# ENTRENADOR16F1939.net
KiCad netlist of a schematic drawn in EAGLE
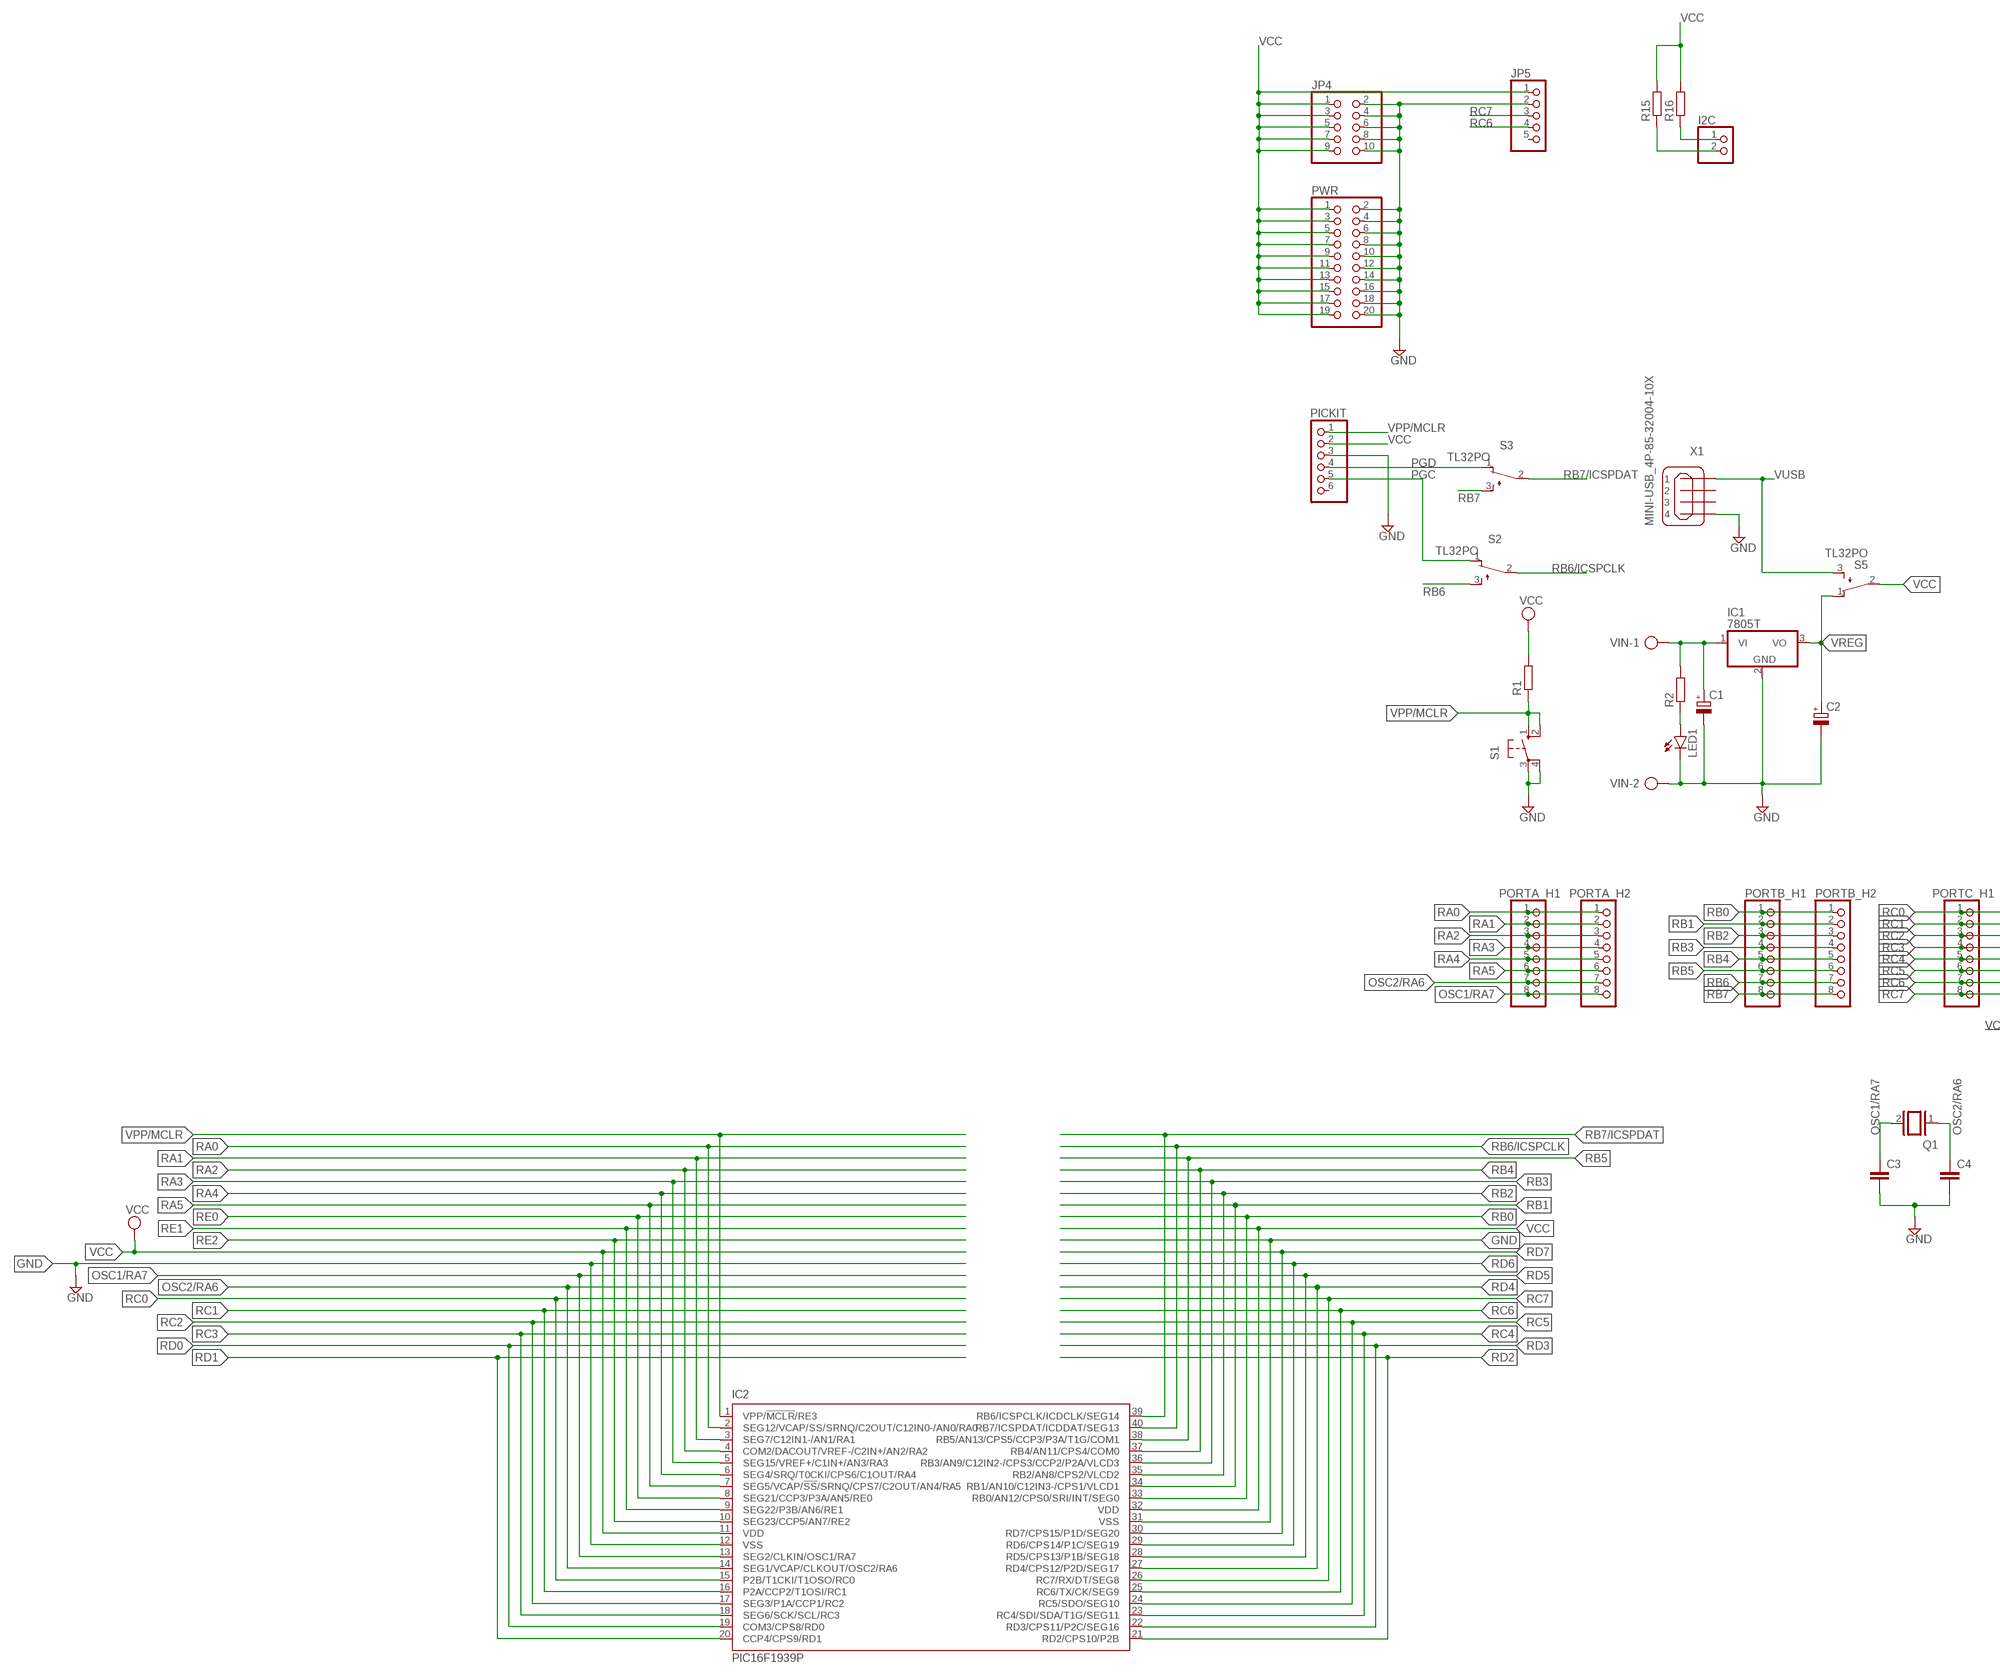
[diagram p0: schematic, sheet 1, part 1 of 2]
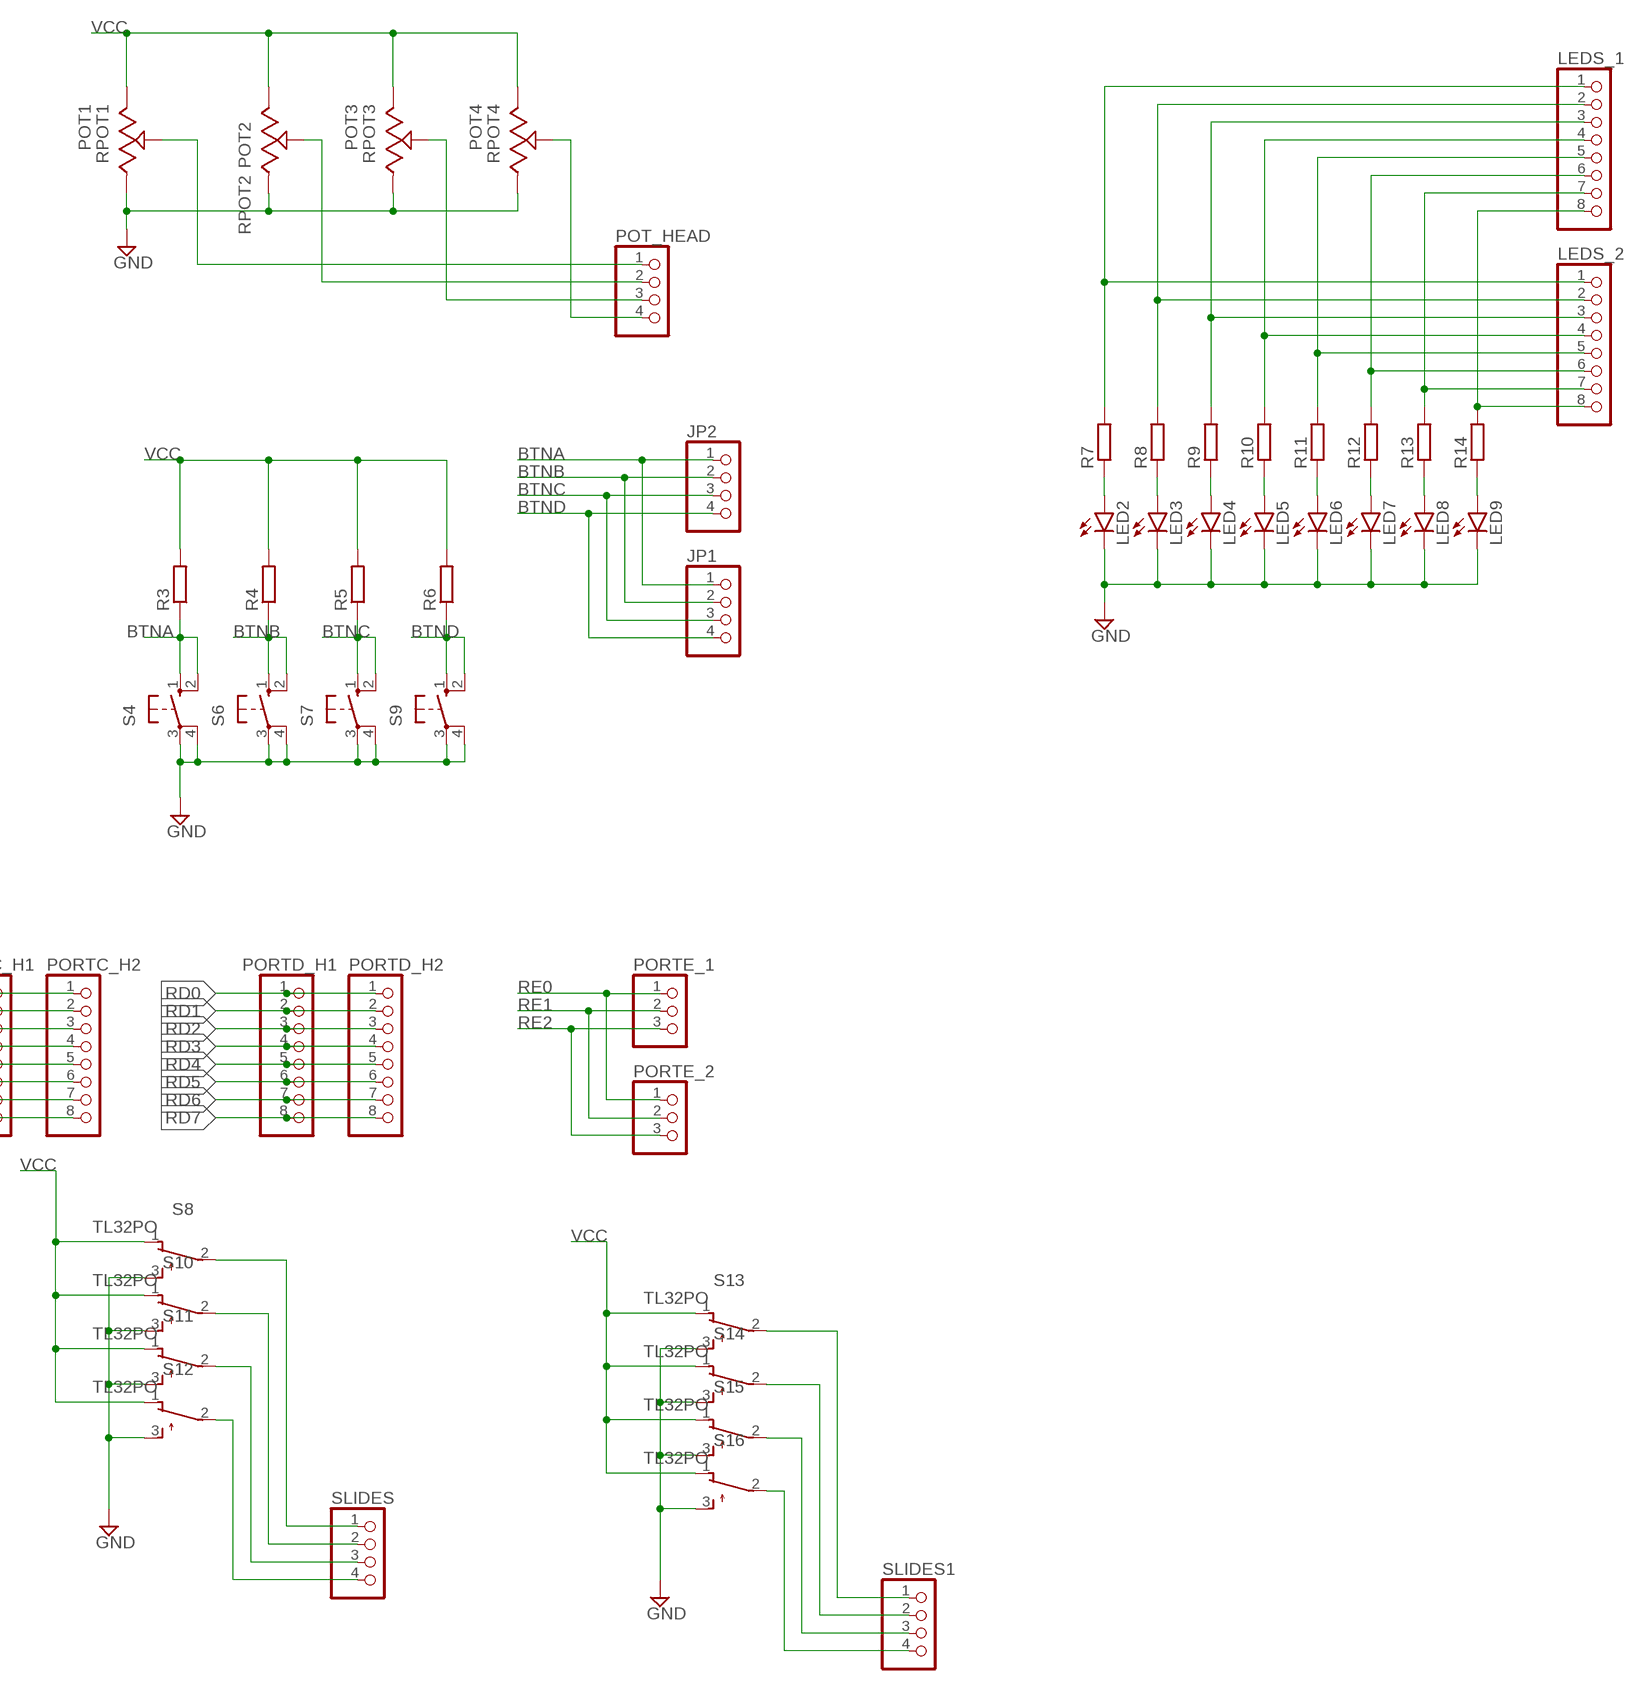
[diagram p1: schematic, sheet 1, part 2 of 2]

(export (version "E")
  (design (tool "Eeschema 10.0.6"))
  (components
    (comp (ref "C1")
      (value "CPOL-EUE2.5-6")
      (footprint "eagle-import:E2,5-6")
      (libsource (lib "eagle-import") (part "CPOL-EUE2.5-6"))
    )
    (comp (ref "C2")
      (value "CPOL-EUE2.5-6")
      (footprint "eagle-import:E2,5-6")
      (libsource (lib "eagle-import") (part "CPOL-EUE2.5-6"))
    )
    (comp (ref "C3")
      (value "C-EU025-024X044")
      (footprint "eagle-import:C025-024X044")
      (libsource (lib "eagle-import") (part "C-EU025-024X044"))
    )
    (comp (ref "C4")
      (value "C-EU025-024X044")
      (footprint "eagle-import:C025-024X044")
      (libsource (lib "eagle-import") (part "C-EU025-024X044"))
    )
    (comp (ref "I2C")
      (value "PINHD-1X2")
      (footprint "eagle-import:1X02")
      (libsource (lib "eagle-import") (part "PINHD-1X2"))
    )
    (comp (ref "IC1")
      (value "7805T")
      (footprint "eagle-import:TO220H")
      (libsource (lib "eagle-import") (part "78T05"))
    )
    (comp (ref "IC2")
      (value "PIC16F1939P")
      (footprint "eagle-import:DIL40")
      (fields (field (name "MPN") "PIC16F1939-I/P"))
      (libsource (lib "eagle-import") (part "PIC16F193?P9"))
    )
    (comp (ref "JP1")
      (value "PINHD-1X4")
      (footprint "eagle-import:1X04")
      (libsource (lib "eagle-import") (part "PINHD-1X4"))
    )
    (comp (ref "JP2")
      (value "PINHD-1X4")
      (footprint "eagle-import:1X04")
      (libsource (lib "eagle-import") (part "PINHD-1X4"))
    )
    (comp (ref "JP4")
      (value "PINHD-2X5")
      (footprint "eagle-import:2X05")
      (libsource (lib "eagle-import") (part "PINHD-2X5"))
    )
    (comp (ref "JP5")
      (value "PINHD-1X5")
      (footprint "eagle-import:1X05")
      (libsource (lib "eagle-import") (part "PINHD-1X5"))
    )
    (comp (ref "LED1")
      (value "LED3MM")
      (footprint "eagle-import:LED3MM")
      (libsource (lib "eagle-import") (part "LED3MM"))
    )
    (comp (ref "LED2")
      (value "LED3MM")
      (footprint "eagle-import:LED3MM")
      (libsource (lib "eagle-import") (part "LED3MM"))
    )
    (comp (ref "LED3")
      (value "LED3MM")
      (footprint "eagle-import:LED3MM")
      (libsource (lib "eagle-import") (part "LED3MM"))
    )
    (comp (ref "LED4")
      (value "LED3MM")
      (footprint "eagle-import:LED3MM")
      (libsource (lib "eagle-import") (part "LED3MM"))
    )
    (comp (ref "LED5")
      (value "LED3MM")
      (footprint "eagle-import:LED3MM")
      (libsource (lib "eagle-import") (part "LED3MM"))
    )
    (comp (ref "LED6")
      (value "LED3MM")
      (footprint "eagle-import:LED3MM")
      (libsource (lib "eagle-import") (part "LED3MM"))
    )
    (comp (ref "LED7")
      (value "LED3MM")
      (footprint "eagle-import:LED3MM")
      (libsource (lib "eagle-import") (part "LED3MM"))
    )
    (comp (ref "LED8")
      (value "LED3MM")
      (footprint "eagle-import:LED3MM")
      (libsource (lib "eagle-import") (part "LED3MM"))
    )
    (comp (ref "LED9")
      (value "LED3MM")
      (footprint "eagle-import:LED3MM")
      (libsource (lib "eagle-import") (part "LED3MM"))
    )
    (comp (ref "LEDS_1")
      (value "PINHD-1X8")
      (footprint "eagle-import:1X08")
      (libsource (lib "eagle-import") (part "PINHD-1X8"))
    )
    (comp (ref "LEDS_2")
      (value "PINHD-1X8")
      (footprint "eagle-import:1X08")
      (libsource (lib "eagle-import") (part "PINHD-1X8"))
    )
    (comp (ref "PICKIT")
      (value "PINHD-1X6")
      (footprint "eagle-import:1X06")
      (libsource (lib "eagle-import") (part "PINHD-1X6"))
    )
    (comp (ref "PORTA_H1")
      (value "PINHD-1X8")
      (footprint "eagle-import:1X08")
      (libsource (lib "eagle-import") (part "PINHD-1X8"))
    )
    (comp (ref "PORTA_H2")
      (value "PINHD-1X8")
      (footprint "eagle-import:1X08")
      (libsource (lib "eagle-import") (part "PINHD-1X8"))
    )
    (comp (ref "PORTB_H1")
      (value "PINHD-1X8")
      (footprint "eagle-import:1X08")
      (libsource (lib "eagle-import") (part "PINHD-1X8"))
    )
    (comp (ref "PORTB_H2")
      (value "PINHD-1X8")
      (footprint "eagle-import:1X08")
      (libsource (lib "eagle-import") (part "PINHD-1X8"))
    )
    (comp (ref "PORTC_H1")
      (value "PINHD-1X8")
      (footprint "eagle-import:1X08")
      (libsource (lib "eagle-import") (part "PINHD-1X8"))
    )
    (comp (ref "PORTC_H2")
      (value "PINHD-1X8")
      (footprint "eagle-import:1X08")
      (libsource (lib "eagle-import") (part "PINHD-1X8"))
    )
    (comp (ref "PORTD_H1")
      (value "PINHD-1X8")
      (footprint "eagle-import:1X08")
      (libsource (lib "eagle-import") (part "PINHD-1X8"))
    )
    (comp (ref "PORTD_H2")
      (value "PINHD-1X8")
      (footprint "eagle-import:1X08")
      (libsource (lib "eagle-import") (part "PINHD-1X8"))
    )
    (comp (ref "PORTE_1")
      (value "PINHD-1X3")
      (footprint "eagle-import:1X03")
      (libsource (lib "eagle-import") (part "PINHD-1X3"))
    )
    (comp (ref "PORTE_2")
      (value "PINHD-1X3")
      (footprint "eagle-import:1X03")
      (libsource (lib "eagle-import") (part "PINHD-1X3"))
    )
    (comp (ref "POT1")
      (value "RPOT1")
      (footprint "eagle-import:TRIM_3386P-1-101TLF")
      (fields (field (name "MF") "Bourns") (field (name "MP") "3386P-1-101TLF"))
      (libsource (lib "eagle-import") (part "3386P-1-101TLF"))
    )
    (comp (ref "POT2")
      (value "RPOT2")
      (footprint "eagle-import:TRIM_3386P-1-101TLF")
      (fields (field (name "MF") "Bourns") (field (name "MP") "3386P-1-101TLF"))
      (libsource (lib "eagle-import") (part "3386P-1-101TLF"))
    )
    (comp (ref "POT3")
      (value "RPOT3")
      (footprint "eagle-import:TRIM_3386P-1-101TLF")
      (fields (field (name "MF") "Bourns") (field (name "MP") "3386P-1-101TLF"))
      (libsource (lib "eagle-import") (part "3386P-1-101TLF"))
    )
    (comp (ref "POT4")
      (value "RPOT4")
      (footprint "eagle-import:TRIM_3386P-1-101TLF")
      (fields (field (name "MF") "Bourns") (field (name "MP") "3386P-1-101TLF"))
      (libsource (lib "eagle-import") (part "3386P-1-101TLF"))
    )
    (comp (ref "POT_HEAD")
      (value "PINHD-1X4")
      (footprint "eagle-import:1X04")
      (libsource (lib "eagle-import") (part "PINHD-1X4"))
    )
    (comp (ref "PWR")
      (value "PINHD-2X10")
      (footprint "eagle-import:2X10")
      (libsource (lib "eagle-import") (part "PINHD-2X10"))
    )
    (comp (ref "Q1")
      (value "XTAL/S")
      (footprint "eagle-import:QS")
      (libsource (lib "eagle-import") (part "XTAL/S"))
    )
    (comp (ref "R1")
      (value "R-EU_0204/7")
      (footprint "eagle-import:0204_7")
      (libsource (lib "eagle-import") (part "R-EU_0204/7"))
    )
    (comp (ref "R2")
      (value "R-EU_0204/7")
      (footprint "eagle-import:0204_7")
      (libsource (lib "eagle-import") (part "R-EU_0204/7"))
    )
    (comp (ref "R3")
      (value "R-EU_0204/7")
      (footprint "eagle-import:0204_7")
      (libsource (lib "eagle-import") (part "R-EU_0204/7"))
    )
    (comp (ref "R4")
      (value "R-EU_0204/7")
      (footprint "eagle-import:0204_7")
      (libsource (lib "eagle-import") (part "R-EU_0204/7"))
    )
    (comp (ref "R5")
      (value "R-EU_0204/7")
      (footprint "eagle-import:0204_7")
      (libsource (lib "eagle-import") (part "R-EU_0204/7"))
    )
    (comp (ref "R6")
      (value "R-EU_0204/7")
      (footprint "eagle-import:0204_7")
      (libsource (lib "eagle-import") (part "R-EU_0204/7"))
    )
    (comp (ref "R7")
      (value "R-EU_0204/7")
      (footprint "eagle-import:0204_7")
      (libsource (lib "eagle-import") (part "R-EU_0204/7"))
    )
    (comp (ref "R8")
      (value "R-EU_0204/7")
      (footprint "eagle-import:0204_7")
      (libsource (lib "eagle-import") (part "R-EU_0204/7"))
    )
    (comp (ref "R9")
      (value "R-EU_0204/7")
      (footprint "eagle-import:0204_7")
      (libsource (lib "eagle-import") (part "R-EU_0204/7"))
    )
    (comp (ref "R10")
      (value "R-EU_0204/7")
      (footprint "eagle-import:0204_7")
      (libsource (lib "eagle-import") (part "R-EU_0204/7"))
    )
    (comp (ref "R11")
      (value "R-EU_0204/7")
      (footprint "eagle-import:0204_7")
      (libsource (lib "eagle-import") (part "R-EU_0204/7"))
    )
    (comp (ref "R12")
      (value "R-EU_0204/7")
      (footprint "eagle-import:0204_7")
      (libsource (lib "eagle-import") (part "R-EU_0204/7"))
    )
    (comp (ref "R13")
      (value "R-EU_0204/7")
      (footprint "eagle-import:0204_7")
      (libsource (lib "eagle-import") (part "R-EU_0204/7"))
    )
    (comp (ref "R14")
      (value "R-EU_0204/7")
      (footprint "eagle-import:0204_7")
      (libsource (lib "eagle-import") (part "R-EU_0204/7"))
    )
    (comp (ref "R15")
      (value "R-EU_0204/7")
      (footprint "eagle-import:0204_7")
      (libsource (lib "eagle-import") (part "R-EU_0204/7"))
    )
    (comp (ref "R16")
      (value "R-EU_0204/7")
      (footprint "eagle-import:0204_7")
      (libsource (lib "eagle-import") (part "R-EU_0204/7"))
    )
    (comp (ref "S1")
      (value "10-XX")
      (footprint "eagle-import:B3F-10XX")
      (fields (field (name "MPN") "B3F-1000"))
      (libsource (lib "eagle-import") (part "10-XX"))
    )
    (comp (ref "S2")
      (value "TL32PO")
      (footprint "eagle-import:TL3XPO")
      (libsource (lib "eagle-import") (part "TL32PO"))
    )
    (comp (ref "S3")
      (value "TL32PO")
      (footprint "eagle-import:TL3XPO")
      (libsource (lib "eagle-import") (part "TL32PO"))
    )
    (comp (ref "S4")
      (value "10-XX")
      (footprint "eagle-import:B3F-10XX")
      (fields (field (name "MPN") "B3F-1000"))
      (libsource (lib "eagle-import") (part "10-XX"))
    )
    (comp (ref "S5")
      (value "TL32PO")
      (footprint "eagle-import:TL3XPO")
      (libsource (lib "eagle-import") (part "TL32PO"))
    )
    (comp (ref "S6")
      (value "10-XX")
      (footprint "eagle-import:B3F-10XX")
      (fields (field (name "MPN") "B3F-1000"))
      (libsource (lib "eagle-import") (part "10-XX"))
    )
    (comp (ref "S7")
      (value "10-XX")
      (footprint "eagle-import:B3F-10XX")
      (fields (field (name "MPN") "B3F-1000"))
      (libsource (lib "eagle-import") (part "10-XX"))
    )
    (comp (ref "S8")
      (value "TL32PO")
      (footprint "eagle-import:TL3XPO")
      (libsource (lib "eagle-import") (part "TL32PO"))
    )
    (comp (ref "S9")
      (value "10-XX")
      (footprint "eagle-import:B3F-10XX")
      (fields (field (name "MPN") "B3F-1000"))
      (libsource (lib "eagle-import") (part "10-XX"))
    )
    (comp (ref "S10")
      (value "TL32PO")
      (footprint "eagle-import:TL3XPO")
      (libsource (lib "eagle-import") (part "TL32PO"))
    )
    (comp (ref "S11")
      (value "TL32PO")
      (footprint "eagle-import:TL3XPO")
      (libsource (lib "eagle-import") (part "TL32PO"))
    )
    (comp (ref "S12")
      (value "TL32PO")
      (footprint "eagle-import:TL3XPO")
      (libsource (lib "eagle-import") (part "TL32PO"))
    )
    (comp (ref "S13")
      (value "TL32PO")
      (footprint "eagle-import:TL3XPO")
      (libsource (lib "eagle-import") (part "TL32PO"))
    )
    (comp (ref "S14")
      (value "TL32PO")
      (footprint "eagle-import:TL3XPO")
      (libsource (lib "eagle-import") (part "TL32PO"))
    )
    (comp (ref "S15")
      (value "TL32PO")
      (footprint "eagle-import:TL3XPO")
      (libsource (lib "eagle-import") (part "TL32PO"))
    )
    (comp (ref "S16")
      (value "TL32PO")
      (footprint "eagle-import:TL3XPO")
      (libsource (lib "eagle-import") (part "TL32PO"))
    )
    (comp (ref "SLIDES")
      (value "PINHD-1X4")
      (footprint "eagle-import:1X04")
      (libsource (lib "eagle-import") (part "PINHD-1X4"))
    )
    (comp (ref "SLIDES1")
      (value "PINHD-1X4")
      (footprint "eagle-import:1X04")
      (libsource (lib "eagle-import") (part "PINHD-1X4"))
    )
    (comp (ref "VIN")
      (value "AK300/2")
      (footprint "eagle-import:AK300_2")
      (libsource (lib "eagle-import") (part "AK300/2"))
    )
    (comp (ref "X1")
      (value "MINI-USB_4P-85-32004-10X")
      (footprint "eagle-import:85-32004-10X")
      (fields (field (name "SPICEPREFIX") "X"))
      (libsource (lib "eagle-import") (part "MINI-USB_4P-85-32004-10X"))
    )
  )
  (nets
    (net (code "1") (name "/BTNA") (class "Default")
      (node (ref "JP1") (pin "1") (pinfunction "1_1") (pintype "passive"))
      (node (ref "JP2") (pin "1") (pinfunction "1_1") (pintype "passive"))
      (node (ref "R3") (pin "1") (pinfunction "1_1") (pintype "passive"))
      (node (ref "S4") (pin "1") (pinfunction "S_1") (pintype "passive"))
      (node (ref "S4") (pin "2") (pinfunction "S1_2") (pintype "passive"))
    )
    (net (code "2") (name "/BTNB") (class "Default")
      (node (ref "JP1") (pin "2") (pinfunction "2_2") (pintype "passive"))
      (node (ref "JP2") (pin "2") (pinfunction "2_2") (pintype "passive"))
      (node (ref "R4") (pin "1") (pinfunction "1_1") (pintype "passive"))
      (node (ref "S6") (pin "1") (pinfunction "S_1") (pintype "passive"))
      (node (ref "S6") (pin "2") (pinfunction "S1_2") (pintype "passive"))
    )
    (net (code "3") (name "/BTNC") (class "Default")
      (node (ref "JP1") (pin "3") (pinfunction "3_3") (pintype "passive"))
      (node (ref "JP2") (pin "3") (pinfunction "3_3") (pintype "passive"))
      (node (ref "R5") (pin "1") (pinfunction "1_1") (pintype "passive"))
      (node (ref "S7") (pin "1") (pinfunction "S_1") (pintype "passive"))
      (node (ref "S7") (pin "2") (pinfunction "S1_2") (pintype "passive"))
    )
    (net (code "4") (name "/BTND") (class "Default")
      (node (ref "JP1") (pin "4") (pinfunction "4_4") (pintype "passive"))
      (node (ref "JP2") (pin "4") (pinfunction "4_4") (pintype "passive"))
      (node (ref "R6") (pin "1") (pinfunction "1_1") (pintype "passive"))
      (node (ref "S9") (pin "1") (pinfunction "S_1") (pintype "passive"))
      (node (ref "S9") (pin "2") (pinfunction "S1_2") (pintype "passive"))
    )
    (net (code "5") (name "/PGC") (class "Default")
      (node (ref "PICKIT") (pin "5") (pinfunction "5_5") (pintype "passive"))
      (node (ref "S2") (pin "1") (pinfunction "O_1") (pintype "passive"))
    )
    (net (code "6") (name "/PGD") (class "Default")
      (node (ref "PICKIT") (pin "4") (pinfunction "4_4") (pintype "passive"))
      (node (ref "S3") (pin "1") (pinfunction "O_1") (pintype "passive"))
    )
    (net (code "7") (name "/VUSB") (class "Default")
      (node (ref "S5") (pin "3") (pinfunction "S_3") (pintype "passive"))
      (node (ref "X1") (pin "1") (pinfunction "1_1") (pintype "passive"))
    )
    (net (code "8") (name "GND") (class "Default")
      (node (ref "C1") (pin "-") (pinfunction "-_-") (pintype "passive"))
      (node (ref "C2") (pin "-") (pinfunction "-_-") (pintype "passive"))
      (node (ref "C3") (pin "2") (pinfunction "2_2") (pintype "passive"))
      (node (ref "C4") (pin "2") (pinfunction "2_2") (pintype "passive"))
      (node (ref "IC1") (pin "2") (pinfunction "GND_2") (pintype "passive"))
      (node (ref "IC2") (pin "12") (pinfunction "VSS_12") (pintype "power_in"))
      (node (ref "IC2") (pin "31") (pinfunction "VSS_31") (pintype "power_in"))
      (node (ref "JP4") (pin "10") (pinfunction "10_10") (pintype "passive"))
      (node (ref "JP4") (pin "2") (pinfunction "2_2") (pintype "passive"))
      (node (ref "JP4") (pin "4") (pinfunction "4_4") (pintype "passive"))
      (node (ref "JP4") (pin "6") (pinfunction "6_6") (pintype "passive"))
      (node (ref "JP4") (pin "8") (pinfunction "8_8") (pintype "passive"))
      (node (ref "JP5") (pin "2") (pinfunction "2_2") (pintype "passive"))
      (node (ref "LED1") (pin "K") (pinfunction "C_K") (pintype "passive"))
      (node (ref "LED2") (pin "K") (pinfunction "C_K") (pintype "passive"))
      (node (ref "LED3") (pin "K") (pinfunction "C_K") (pintype "passive"))
      (node (ref "LED4") (pin "K") (pinfunction "C_K") (pintype "passive"))
      (node (ref "LED5") (pin "K") (pinfunction "C_K") (pintype "passive"))
      (node (ref "LED6") (pin "K") (pinfunction "C_K") (pintype "passive"))
      (node (ref "LED7") (pin "K") (pinfunction "C_K") (pintype "passive"))
      (node (ref "LED8") (pin "K") (pinfunction "C_K") (pintype "passive"))
      (node (ref "LED9") (pin "K") (pinfunction "C_K") (pintype "passive"))
      (node (ref "PICKIT") (pin "3") (pinfunction "3_3") (pintype "passive"))
      (node (ref "POT1") (pin "3") (pinfunction "CW_3") (pintype "passive"))
      (node (ref "POT2") (pin "3") (pinfunction "CW_3") (pintype "passive"))
      (node (ref "POT3") (pin "3") (pinfunction "CW_3") (pintype "passive"))
      (node (ref "POT4") (pin "3") (pinfunction "CW_3") (pintype "passive"))
      (node (ref "PWR") (pin "10") (pinfunction "10_10") (pintype "passive"))
      (node (ref "PWR") (pin "12") (pinfunction "12_12") (pintype "passive"))
      (node (ref "PWR") (pin "14") (pinfunction "14_14") (pintype "passive"))
      (node (ref "PWR") (pin "16") (pinfunction "16_16") (pintype "passive"))
      (node (ref "PWR") (pin "18") (pinfunction "18_18") (pintype "passive"))
      (node (ref "PWR") (pin "2") (pinfunction "2_2") (pintype "passive"))
      (node (ref "PWR") (pin "20") (pinfunction "20_20") (pintype "passive"))
      (node (ref "PWR") (pin "4") (pinfunction "4_4") (pintype "passive"))
      (node (ref "PWR") (pin "6") (pinfunction "6_6") (pintype "passive"))
      (node (ref "PWR") (pin "8") (pinfunction "8_8") (pintype "passive"))
      (node (ref "S1") (pin "3") (pinfunction "P_3") (pintype "passive"))
      (node (ref "S1") (pin "4") (pinfunction "P1_4") (pintype "passive"))
      (node (ref "S10") (pin "3") (pinfunction "S_3") (pintype "passive"))
      (node (ref "S11") (pin "3") (pinfunction "S_3") (pintype "passive"))
      (node (ref "S12") (pin "3") (pinfunction "S_3") (pintype "passive"))
      (node (ref "S13") (pin "3") (pinfunction "S_3") (pintype "passive"))
      (node (ref "S14") (pin "3") (pinfunction "S_3") (pintype "passive"))
      (node (ref "S15") (pin "3") (pinfunction "S_3") (pintype "passive"))
      (node (ref "S16") (pin "3") (pinfunction "S_3") (pintype "passive"))
      (node (ref "S4") (pin "3") (pinfunction "P_3") (pintype "passive"))
      (node (ref "S4") (pin "4") (pinfunction "P1_4") (pintype "passive"))
      (node (ref "S6") (pin "3") (pinfunction "P_3") (pintype "passive"))
      (node (ref "S6") (pin "4") (pinfunction "P1_4") (pintype "passive"))
      (node (ref "S7") (pin "3") (pinfunction "P_3") (pintype "passive"))
      (node (ref "S7") (pin "4") (pinfunction "P1_4") (pintype "passive"))
      (node (ref "S8") (pin "3") (pinfunction "S_3") (pintype "passive"))
      (node (ref "S9") (pin "3") (pinfunction "P_3") (pintype "passive"))
      (node (ref "S9") (pin "4") (pinfunction "P1_4") (pintype "passive"))
      (node (ref "VIN") (pin "2") (pinfunction "KL_2") (pintype "passive"))
      (node (ref "X1") (pin "4") (pinfunction "4_4") (pintype "passive"))
    )
    (net (code "9") (name "Net-(I2C-Pad1)") (class "Default")
      (node (ref "I2C") (pin "1") (pinfunction "1_1") (pintype "passive"))
      (node (ref "R16") (pin "1") (pinfunction "1_1") (pintype "passive"))
    )
    (net (code "10") (name "Net-(I2C-Pad2)") (class "Default")
      (node (ref "I2C") (pin "2") (pinfunction "2_2") (pintype "passive"))
      (node (ref "R15") (pin "1") (pinfunction "1_1") (pintype "passive"))
    )
    (net (code "11") (name "Net-(IC1-VI)") (class "Default")
      (node (ref "C1") (pin "+") (pinfunction "+_+") (pintype "passive"))
      (node (ref "IC1") (pin "1") (pinfunction "VI_1") (pintype "input"))
      (node (ref "R2") (pin "2") (pinfunction "2_2") (pintype "passive"))
      (node (ref "VIN") (pin "1") (pinfunction "KL_1") (pintype "passive"))
    )
    (net (code "12") (name "Net-(LED1-PadA)") (class "Default")
      (node (ref "LED1") (pin "A") (pinfunction "A_A") (pintype "passive"))
      (node (ref "R2") (pin "1") (pinfunction "1_1") (pintype "passive"))
    )
    (net (code "13") (name "Net-(LED2-PadA)") (class "Default")
      (node (ref "LED2") (pin "A") (pinfunction "A_A") (pintype "passive"))
      (node (ref "R7") (pin "1") (pinfunction "1_1") (pintype "passive"))
    )
    (net (code "14") (name "Net-(LED3-PadA)") (class "Default")
      (node (ref "LED3") (pin "A") (pinfunction "A_A") (pintype "passive"))
      (node (ref "R8") (pin "1") (pinfunction "1_1") (pintype "passive"))
    )
    (net (code "15") (name "Net-(LED4-PadA)") (class "Default")
      (node (ref "LED4") (pin "A") (pinfunction "A_A") (pintype "passive"))
      (node (ref "R9") (pin "1") (pinfunction "1_1") (pintype "passive"))
    )
    (net (code "16") (name "Net-(LED5-PadA)") (class "Default")
      (node (ref "LED5") (pin "A") (pinfunction "A_A") (pintype "passive"))
      (node (ref "R10") (pin "1") (pinfunction "1_1") (pintype "passive"))
    )
    (net (code "17") (name "Net-(LED6-PadA)") (class "Default")
      (node (ref "LED6") (pin "A") (pinfunction "A_A") (pintype "passive"))
      (node (ref "R11") (pin "1") (pinfunction "1_1") (pintype "passive"))
    )
    (net (code "18") (name "Net-(LED7-PadA)") (class "Default")
      (node (ref "LED7") (pin "A") (pinfunction "A_A") (pintype "passive"))
      (node (ref "R12") (pin "1") (pinfunction "1_1") (pintype "passive"))
    )
    (net (code "19") (name "Net-(LED8-PadA)") (class "Default")
      (node (ref "LED8") (pin "A") (pinfunction "A_A") (pintype "passive"))
      (node (ref "R13") (pin "1") (pinfunction "1_1") (pintype "passive"))
    )
    (net (code "20") (name "Net-(LED9-PadA)") (class "Default")
      (node (ref "LED9") (pin "A") (pinfunction "A_A") (pintype "passive"))
      (node (ref "R14") (pin "1") (pinfunction "1_1") (pintype "passive"))
    )
    (net (code "21") (name "Net-(LEDS_1-Pad1)") (class "Default")
      (node (ref "LEDS_1") (pin "1") (pinfunction "1_1") (pintype "passive"))
      (node (ref "LEDS_2") (pin "1") (pinfunction "1_1") (pintype "passive"))
      (node (ref "R7") (pin "2") (pinfunction "2_2") (pintype "passive"))
    )
    (net (code "22") (name "Net-(LEDS_1-Pad2)") (class "Default")
      (node (ref "LEDS_1") (pin "2") (pinfunction "2_2") (pintype "passive"))
      (node (ref "LEDS_2") (pin "2") (pinfunction "2_2") (pintype "passive"))
      (node (ref "R8") (pin "2") (pinfunction "2_2") (pintype "passive"))
    )
    (net (code "23") (name "Net-(LEDS_1-Pad3)") (class "Default")
      (node (ref "LEDS_1") (pin "3") (pinfunction "3_3") (pintype "passive"))
      (node (ref "LEDS_2") (pin "3") (pinfunction "3_3") (pintype "passive"))
      (node (ref "R9") (pin "2") (pinfunction "2_2") (pintype "passive"))
    )
    (net (code "24") (name "Net-(LEDS_1-Pad4)") (class "Default")
      (node (ref "LEDS_1") (pin "4") (pinfunction "4_4") (pintype "passive"))
      (node (ref "LEDS_2") (pin "4") (pinfunction "4_4") (pintype "passive"))
      (node (ref "R10") (pin "2") (pinfunction "2_2") (pintype "passive"))
    )
    (net (code "25") (name "Net-(LEDS_1-Pad5)") (class "Default")
      (node (ref "LEDS_1") (pin "5") (pinfunction "5_5") (pintype "passive"))
      (node (ref "LEDS_2") (pin "5") (pinfunction "5_5") (pintype "passive"))
      (node (ref "R11") (pin "2") (pinfunction "2_2") (pintype "passive"))
    )
    (net (code "26") (name "Net-(LEDS_1-Pad6)") (class "Default")
      (node (ref "LEDS_1") (pin "6") (pinfunction "6_6") (pintype "passive"))
      (node (ref "LEDS_2") (pin "6") (pinfunction "6_6") (pintype "passive"))
      (node (ref "R12") (pin "2") (pinfunction "2_2") (pintype "passive"))
    )
    (net (code "27") (name "Net-(LEDS_1-Pad7)") (class "Default")
      (node (ref "LEDS_1") (pin "7") (pinfunction "7_7") (pintype "passive"))
      (node (ref "LEDS_2") (pin "7") (pinfunction "7_7") (pintype "passive"))
      (node (ref "R13") (pin "2") (pinfunction "2_2") (pintype "passive"))
    )
    (net (code "28") (name "Net-(LEDS_1-Pad8)") (class "Default")
      (node (ref "LEDS_1") (pin "8") (pinfunction "8_8") (pintype "passive"))
      (node (ref "LEDS_2") (pin "8") (pinfunction "8_8") (pintype "passive"))
      (node (ref "R14") (pin "2") (pinfunction "2_2") (pintype "passive"))
    )
    (net (code "29") (name "Net-(POT1-WIPER)") (class "Default")
      (node (ref "POT1") (pin "2") (pinfunction "WIPER_2") (pintype "passive"))
      (node (ref "POT_HEAD") (pin "1") (pinfunction "1_1") (pintype "passive"))
    )
    (net (code "30") (name "Net-(POT2-WIPER)") (class "Default")
      (node (ref "POT2") (pin "2") (pinfunction "WIPER_2") (pintype "passive"))
      (node (ref "POT_HEAD") (pin "2") (pinfunction "2_2") (pintype "passive"))
    )
    (net (code "31") (name "Net-(POT3-WIPER)") (class "Default")
      (node (ref "POT3") (pin "2") (pinfunction "WIPER_2") (pintype "passive"))
      (node (ref "POT_HEAD") (pin "3") (pinfunction "3_3") (pintype "passive"))
    )
    (net (code "32") (name "Net-(POT4-WIPER)") (class "Default")
      (node (ref "POT4") (pin "2") (pinfunction "WIPER_2") (pintype "passive"))
      (node (ref "POT_HEAD") (pin "4") (pinfunction "4_4") (pintype "passive"))
    )
    (net (code "33") (name "Net-(S8-P)") (class "Default")
      (node (ref "S8") (pin "2") (pinfunction "P_2") (pintype "passive"))
      (node (ref "SLIDES") (pin "1") (pinfunction "1_1") (pintype "passive"))
    )
    (net (code "34") (name "Net-(S10-P)") (class "Default")
      (node (ref "S10") (pin "2") (pinfunction "P_2") (pintype "passive"))
      (node (ref "SLIDES") (pin "2") (pinfunction "2_2") (pintype "passive"))
    )
    (net (code "35") (name "Net-(S11-P)") (class "Default")
      (node (ref "S11") (pin "2") (pinfunction "P_2") (pintype "passive"))
      (node (ref "SLIDES") (pin "3") (pinfunction "3_3") (pintype "passive"))
    )
    (net (code "36") (name "Net-(S12-P)") (class "Default")
      (node (ref "S12") (pin "2") (pinfunction "P_2") (pintype "passive"))
      (node (ref "SLIDES") (pin "4") (pinfunction "4_4") (pintype "passive"))
    )
    (net (code "37") (name "Net-(S13-P)") (class "Default")
      (node (ref "S13") (pin "2") (pinfunction "P_2") (pintype "passive"))
      (node (ref "SLIDES1") (pin "1") (pinfunction "1_1") (pintype "passive"))
    )
    (net (code "38") (name "Net-(S14-P)") (class "Default")
      (node (ref "S14") (pin "2") (pinfunction "P_2") (pintype "passive"))
      (node (ref "SLIDES1") (pin "2") (pinfunction "2_2") (pintype "passive"))
    )
    (net (code "39") (name "Net-(S15-P)") (class "Default")
      (node (ref "S15") (pin "2") (pinfunction "P_2") (pintype "passive"))
      (node (ref "SLIDES1") (pin "3") (pinfunction "3_3") (pintype "passive"))
    )
    (net (code "40") (name "Net-(S16-P)") (class "Default")
      (node (ref "S16") (pin "2") (pinfunction "P_2") (pintype "passive"))
      (node (ref "SLIDES1") (pin "4") (pinfunction "4_4") (pintype "passive"))
    )
    (net (code "41") (name "OSC1{slash}RA7") (class "Default")
      (node (ref "C3") (pin "1") (pinfunction "1_1") (pintype "passive"))
      (node (ref "IC2") (pin "13") (pinfunction "SEG2/CLKIN/OSC1/RA7_13") (pintype "bidirectional"))
      (node (ref "PORTA_H1") (pin "8") (pinfunction "8_8") (pintype "passive"))
      (node (ref "PORTA_H2") (pin "8") (pinfunction "8_8") (pintype "passive"))
      (node (ref "Q1") (pin "2") (pinfunction "2_2") (pintype "passive"))
    )
    (net (code "42") (name "OSC2{slash}RA6") (class "Default")
      (node (ref "C4") (pin "1") (pinfunction "1_1") (pintype "passive"))
      (node (ref "IC2") (pin "14") (pinfunction "SEG1/VCAP/CLKOUT/OSC2/RA6_14") (pintype "bidirectional"))
      (node (ref "PORTA_H1") (pin "7") (pinfunction "7_7") (pintype "passive"))
      (node (ref "PORTA_H2") (pin "7") (pinfunction "7_7") (pintype "passive"))
      (node (ref "Q1") (pin "1") (pinfunction "1_1") (pintype "passive"))
    )
    (net (code "43") (name "RA0") (class "Default")
      (node (ref "IC2") (pin "2") (pinfunction "SEG12/VCAP/SS/SRNQ/C2OUT/C12IN0-/AN0/RA0_2") (pintype "bidirectional"))
      (node (ref "PORTA_H1") (pin "1") (pinfunction "1_1") (pintype "passive"))
      (node (ref "PORTA_H2") (pin "1") (pinfunction "1_1") (pintype "passive"))
    )
    (net (code "44") (name "RA1") (class "Default")
      (node (ref "IC2") (pin "3") (pinfunction "SEG7/C12IN1-/AN1/RA1_3") (pintype "bidirectional"))
      (node (ref "PORTA_H1") (pin "2") (pinfunction "2_2") (pintype "passive"))
      (node (ref "PORTA_H2") (pin "2") (pinfunction "2_2") (pintype "passive"))
    )
    (net (code "45") (name "RA2") (class "Default")
      (node (ref "IC2") (pin "4") (pinfunction "COM2/DACOUT/VREF-/C2IN+/AN2/RA2_4") (pintype "bidirectional"))
      (node (ref "PORTA_H1") (pin "3") (pinfunction "3_3") (pintype "passive"))
      (node (ref "PORTA_H2") (pin "3") (pinfunction "3_3") (pintype "passive"))
    )
    (net (code "46") (name "RA3") (class "Default")
      (node (ref "IC2") (pin "5") (pinfunction "SEG15/VREF+/C1IN+/AN3/RA3_5") (pintype "bidirectional"))
      (node (ref "PORTA_H1") (pin "4") (pinfunction "4_4") (pintype "passive"))
      (node (ref "PORTA_H2") (pin "4") (pinfunction "4_4") (pintype "passive"))
    )
    (net (code "47") (name "RA4") (class "Default")
      (node (ref "IC2") (pin "6") (pinfunction "SEG4/SRQ/T0CKI/CPS6/C1OUT/RA4_6") (pintype "bidirectional"))
      (node (ref "PORTA_H1") (pin "5") (pinfunction "5_5") (pintype "passive"))
      (node (ref "PORTA_H2") (pin "5") (pinfunction "5_5") (pintype "passive"))
    )
    (net (code "48") (name "RA5") (class "Default")
      (node (ref "IC2") (pin "7") (pinfunction "SEG5/VCAP/~{SS}/SRNQ/CPS7/C2OUT/AN4/RA5_7") (pintype "bidirectional"))
      (node (ref "PORTA_H1") (pin "6") (pinfunction "6_6") (pintype "passive"))
      (node (ref "PORTA_H2") (pin "6") (pinfunction "6_6") (pintype "passive"))
    )
    (net (code "49") (name "RB0") (class "Default")
      (node (ref "IC2") (pin "33") (pinfunction "RB0/AN12/CPS0/SRI/INT/SEG0_33") (pintype "bidirectional"))
      (node (ref "PORTB_H1") (pin "1") (pinfunction "1_1") (pintype "passive"))
      (node (ref "PORTB_H2") (pin "1") (pinfunction "1_1") (pintype "passive"))
    )
    (net (code "50") (name "RB1") (class "Default")
      (node (ref "IC2") (pin "34") (pinfunction "RB1/AN10/C12IN3-/CPS1/VLCD1_34") (pintype "bidirectional"))
      (node (ref "PORTB_H1") (pin "2") (pinfunction "2_2") (pintype "passive"))
      (node (ref "PORTB_H2") (pin "2") (pinfunction "2_2") (pintype "passive"))
    )
    (net (code "51") (name "RB2") (class "Default")
      (node (ref "IC2") (pin "35") (pinfunction "RB2/AN8/CPS2/VLCD2_35") (pintype "bidirectional"))
      (node (ref "PORTB_H1") (pin "3") (pinfunction "3_3") (pintype "passive"))
      (node (ref "PORTB_H2") (pin "3") (pinfunction "3_3") (pintype "passive"))
    )
    (net (code "52") (name "RB3") (class "Default")
      (node (ref "IC2") (pin "36") (pinfunction "RB3/AN9/C12IN2-/CPS3/CCP2/P2A/VLCD3_36") (pintype "bidirectional"))
      (node (ref "PORTB_H1") (pin "4") (pinfunction "4_4") (pintype "passive"))
      (node (ref "PORTB_H2") (pin "4") (pinfunction "4_4") (pintype "passive"))
    )
    (net (code "53") (name "RB4") (class "Default")
      (node (ref "IC2") (pin "37") (pinfunction "RB4/AN11/CPS4/COM0_37") (pintype "bidirectional"))
      (node (ref "PORTB_H1") (pin "5") (pinfunction "5_5") (pintype "passive"))
      (node (ref "PORTB_H2") (pin "5") (pinfunction "5_5") (pintype "passive"))
    )
    (net (code "54") (name "RB5") (class "Default")
      (node (ref "IC2") (pin "38") (pinfunction "RB5/AN13/CPS5/CCP3/P3A/T1G/COM1_38") (pintype "bidirectional"))
      (node (ref "PORTB_H1") (pin "6") (pinfunction "6_6") (pintype "passive"))
      (node (ref "PORTB_H2") (pin "6") (pinfunction "6_6") (pintype "passive"))
    )
    (net (code "55") (name "RB6") (class "Default")
      (node (ref "PORTB_H1") (pin "7") (pinfunction "7_7") (pintype "passive"))
      (node (ref "PORTB_H2") (pin "7") (pinfunction "7_7") (pintype "passive"))
      (node (ref "S2") (pin "3") (pinfunction "S_3") (pintype "passive"))
    )
    (net (code "56") (name "RB6{slash}ICSPCLK") (class "Default")
      (node (ref "IC2") (pin "40") (pinfunction "RB7/ICSPDAT/ICDDAT/SEG13_40") (pintype "bidirectional"))
      (node (ref "S2") (pin "2") (pinfunction "P_2") (pintype "passive"))
    )
    (net (code "57") (name "RB7") (class "Default")
      (node (ref "PORTB_H1") (pin "8") (pinfunction "8_8") (pintype "passive"))
      (node (ref "PORTB_H2") (pin "8") (pinfunction "8_8") (pintype "passive"))
      (node (ref "S3") (pin "3") (pinfunction "S_3") (pintype "passive"))
    )
    (net (code "58") (name "RB7{slash}ICSPDAT") (class "Default")
      (node (ref "IC2") (pin "39") (pinfunction "RB6/ICSPCLK/ICDCLK/SEG14_39") (pintype "bidirectional"))
      (node (ref "S3") (pin "2") (pinfunction "P_2") (pintype "passive"))
    )
    (net (code "59") (name "RC0") (class "Default")
      (node (ref "IC2") (pin "15") (pinfunction "P2B/T1CKI/T1OSO/RC0_15") (pintype "bidirectional"))
      (node (ref "PORTC_H1") (pin "1") (pinfunction "1_1") (pintype "passive"))
      (node (ref "PORTC_H2") (pin "1") (pinfunction "1_1") (pintype "passive"))
    )
    (net (code "60") (name "RC1") (class "Default")
      (node (ref "IC2") (pin "16") (pinfunction "P2A/CCP2/T1OSI/RC1_16") (pintype "bidirectional"))
      (node (ref "PORTC_H1") (pin "2") (pinfunction "2_2") (pintype "passive"))
      (node (ref "PORTC_H2") (pin "2") (pinfunction "2_2") (pintype "passive"))
    )
    (net (code "61") (name "RC2") (class "Default")
      (node (ref "IC2") (pin "17") (pinfunction "SEG3/P1A/CCP1/RC2_17") (pintype "bidirectional"))
      (node (ref "PORTC_H1") (pin "3") (pinfunction "3_3") (pintype "passive"))
      (node (ref "PORTC_H2") (pin "3") (pinfunction "3_3") (pintype "passive"))
    )
    (net (code "62") (name "RC3") (class "Default")
      (node (ref "IC2") (pin "18") (pinfunction "SEG6/SCK/SCL/RC3_18") (pintype "bidirectional"))
      (node (ref "PORTC_H1") (pin "4") (pinfunction "4_4") (pintype "passive"))
      (node (ref "PORTC_H2") (pin "4") (pinfunction "4_4") (pintype "passive"))
    )
    (net (code "63") (name "RC4") (class "Default")
      (node (ref "IC2") (pin "23") (pinfunction "RC4/SDI/SDA/T1G/SEG11_23") (pintype "bidirectional"))
      (node (ref "PORTC_H1") (pin "5") (pinfunction "5_5") (pintype "passive"))
      (node (ref "PORTC_H2") (pin "5") (pinfunction "5_5") (pintype "passive"))
    )
    (net (code "64") (name "RC5") (class "Default")
      (node (ref "IC2") (pin "24") (pinfunction "RC5/SDO/SEG10_24") (pintype "bidirectional"))
      (node (ref "PORTC_H1") (pin "6") (pinfunction "6_6") (pintype "passive"))
      (node (ref "PORTC_H2") (pin "6") (pinfunction "6_6") (pintype "passive"))
    )
    (net (code "65") (name "RC6") (class "Default")
      (node (ref "IC2") (pin "25") (pinfunction "RC6/TX/CK/SEG9_25") (pintype "bidirectional"))
      (node (ref "JP5") (pin "4") (pinfunction "4_4") (pintype "passive"))
      (node (ref "PORTC_H1") (pin "7") (pinfunction "7_7") (pintype "passive"))
      (node (ref "PORTC_H2") (pin "7") (pinfunction "7_7") (pintype "passive"))
    )
    (net (code "66") (name "RC7") (class "Default")
      (node (ref "IC2") (pin "26") (pinfunction "RC7/RX/DT/SEG8_26") (pintype "bidirectional"))
      (node (ref "JP5") (pin "3") (pinfunction "3_3") (pintype "passive"))
      (node (ref "PORTC_H1") (pin "8") (pinfunction "8_8") (pintype "passive"))
      (node (ref "PORTC_H2") (pin "8") (pinfunction "8_8") (pintype "passive"))
    )
    (net (code "67") (name "RD0") (class "Default")
      (node (ref "IC2") (pin "19") (pinfunction "COM3/CPS8/RD0_19") (pintype "bidirectional"))
      (node (ref "PORTD_H1") (pin "1") (pinfunction "1_1") (pintype "passive"))
      (node (ref "PORTD_H2") (pin "1") (pinfunction "1_1") (pintype "passive"))
    )
    (net (code "68") (name "RD1") (class "Default")
      (node (ref "IC2") (pin "20") (pinfunction "CCP4/CPS9/RD1_20") (pintype "bidirectional"))
      (node (ref "PORTD_H1") (pin "2") (pinfunction "2_2") (pintype "passive"))
      (node (ref "PORTD_H2") (pin "2") (pinfunction "2_2") (pintype "passive"))
    )
    (net (code "69") (name "RD2") (class "Default")
      (node (ref "IC2") (pin "21") (pinfunction "RD2/CPS10/P2B_21") (pintype "bidirectional"))
      (node (ref "PORTD_H1") (pin "3") (pinfunction "3_3") (pintype "passive"))
      (node (ref "PORTD_H2") (pin "3") (pinfunction "3_3") (pintype "passive"))
    )
    (net (code "70") (name "RD3") (class "Default")
      (node (ref "IC2") (pin "22") (pinfunction "RD3/CPS11/P2C/SEG16_22") (pintype "bidirectional"))
      (node (ref "PORTD_H1") (pin "4") (pinfunction "4_4") (pintype "passive"))
      (node (ref "PORTD_H2") (pin "4") (pinfunction "4_4") (pintype "passive"))
    )
    (net (code "71") (name "RD4") (class "Default")
      (node (ref "IC2") (pin "27") (pinfunction "RD4/CPS12/P2D/SEG17_27") (pintype "bidirectional"))
      (node (ref "PORTD_H1") (pin "5") (pinfunction "5_5") (pintype "passive"))
      (node (ref "PORTD_H2") (pin "5") (pinfunction "5_5") (pintype "passive"))
    )
    (net (code "72") (name "RD5") (class "Default")
      (node (ref "IC2") (pin "28") (pinfunction "RD5/CPS13/P1B/SEG18_28") (pintype "bidirectional"))
      (node (ref "PORTD_H1") (pin "6") (pinfunction "6_6") (pintype "passive"))
      (node (ref "PORTD_H2") (pin "6") (pinfunction "6_6") (pintype "passive"))
    )
    (net (code "73") (name "RD6") (class "Default")
      (node (ref "IC2") (pin "29") (pinfunction "RD6/CPS14/P1C/SEG19_29") (pintype "bidirectional"))
      (node (ref "PORTD_H1") (pin "7") (pinfunction "7_7") (pintype "passive"))
      (node (ref "PORTD_H2") (pin "7") (pinfunction "7_7") (pintype "passive"))
    )
    (net (code "74") (name "RD7") (class "Default")
      (node (ref "IC2") (pin "30") (pinfunction "RD7/CPS15/P1D/SEG20_30") (pintype "bidirectional"))
      (node (ref "PORTD_H1") (pin "8") (pinfunction "8_8") (pintype "passive"))
      (node (ref "PORTD_H2") (pin "8") (pinfunction "8_8") (pintype "passive"))
    )
    (net (code "75") (name "RE0") (class "Default")
      (node (ref "IC2") (pin "8") (pinfunction "SEG21/CCP3/P3A/AN5/RE0_8") (pintype "bidirectional"))
      (node (ref "PORTE_1") (pin "1") (pinfunction "1_1") (pintype "passive"))
      (node (ref "PORTE_2") (pin "1") (pinfunction "1_1") (pintype "passive"))
    )
    (net (code "76") (name "RE1") (class "Default")
      (node (ref "IC2") (pin "9") (pinfunction "SEG22/P3B/AN6/RE1_9") (pintype "bidirectional"))
      (node (ref "PORTE_1") (pin "2") (pinfunction "2_2") (pintype "passive"))
      (node (ref "PORTE_2") (pin "2") (pinfunction "2_2") (pintype "passive"))
    )
    (net (code "77") (name "RE2") (class "Default")
      (node (ref "IC2") (pin "10") (pinfunction "SEG23/CCP5/AN7/RE2_10") (pintype "bidirectional"))
      (node (ref "PORTE_1") (pin "3") (pinfunction "3_3") (pintype "passive"))
      (node (ref "PORTE_2") (pin "3") (pinfunction "3_3") (pintype "passive"))
    )
    (net (code "78") (name "VCC") (class "Default")
      (node (ref "IC2") (pin "11") (pinfunction "VDD_11") (pintype "power_in"))
      (node (ref "IC2") (pin "32") (pinfunction "VDD_32") (pintype "power_in"))
      (node (ref "JP4") (pin "1") (pinfunction "1_1") (pintype "passive"))
      (node (ref "JP4") (pin "3") (pinfunction "3_3") (pintype "passive"))
      (node (ref "JP4") (pin "5") (pinfunction "5_5") (pintype "passive"))
      (node (ref "JP4") (pin "7") (pinfunction "7_7") (pintype "passive"))
      (node (ref "JP4") (pin "9") (pinfunction "9_9") (pintype "passive"))
      (node (ref "JP5") (pin "1") (pinfunction "1_1") (pintype "passive"))
      (node (ref "PICKIT") (pin "2") (pinfunction "2_2") (pintype "passive"))
      (node (ref "POT1") (pin "1") (pinfunction "CCW_1") (pintype "passive"))
      (node (ref "POT2") (pin "1") (pinfunction "CCW_1") (pintype "passive"))
      (node (ref "POT3") (pin "1") (pinfunction "CCW_1") (pintype "passive"))
      (node (ref "POT4") (pin "1") (pinfunction "CCW_1") (pintype "passive"))
      (node (ref "PWR") (pin "1") (pinfunction "1_1") (pintype "passive"))
      (node (ref "PWR") (pin "11") (pinfunction "11_11") (pintype "passive"))
      (node (ref "PWR") (pin "13") (pinfunction "13_13") (pintype "passive"))
      (node (ref "PWR") (pin "15") (pinfunction "15_15") (pintype "passive"))
      (node (ref "PWR") (pin "17") (pinfunction "17_17") (pintype "passive"))
      (node (ref "PWR") (pin "19") (pinfunction "19_19") (pintype "passive"))
      (node (ref "PWR") (pin "3") (pinfunction "3_3") (pintype "passive"))
      (node (ref "PWR") (pin "5") (pinfunction "5_5") (pintype "passive"))
      (node (ref "PWR") (pin "7") (pinfunction "7_7") (pintype "passive"))
      (node (ref "PWR") (pin "9") (pinfunction "9_9") (pintype "passive"))
      (node (ref "R1") (pin "2") (pinfunction "2_2") (pintype "passive"))
      (node (ref "R15") (pin "2") (pinfunction "2_2") (pintype "passive"))
      (node (ref "R16") (pin "2") (pinfunction "2_2") (pintype "passive"))
      (node (ref "R3") (pin "2") (pinfunction "2_2") (pintype "passive"))
      (node (ref "R4") (pin "2") (pinfunction "2_2") (pintype "passive"))
      (node (ref "R5") (pin "2") (pinfunction "2_2") (pintype "passive"))
      (node (ref "R6") (pin "2") (pinfunction "2_2") (pintype "passive"))
      (node (ref "S10") (pin "1") (pinfunction "O_1") (pintype "passive"))
      (node (ref "S11") (pin "1") (pinfunction "O_1") (pintype "passive"))
      (node (ref "S12") (pin "1") (pinfunction "O_1") (pintype "passive"))
      (node (ref "S13") (pin "1") (pinfunction "O_1") (pintype "passive"))
      (node (ref "S14") (pin "1") (pinfunction "O_1") (pintype "passive"))
      (node (ref "S15") (pin "1") (pinfunction "O_1") (pintype "passive"))
      (node (ref "S16") (pin "1") (pinfunction "O_1") (pintype "passive"))
      (node (ref "S5") (pin "2") (pinfunction "P_2") (pintype "passive"))
      (node (ref "S8") (pin "1") (pinfunction "O_1") (pintype "passive"))
    )
    (net (code "79") (name "VPP{slash}MCLR") (class "Default")
      (node (ref "IC2") (pin "1") (pinfunction "VPP/~{MCLR}/RE3_1") (pintype "input"))
      (node (ref "PICKIT") (pin "1") (pinfunction "1_1") (pintype "passive"))
      (node (ref "R1") (pin "1") (pinfunction "1_1") (pintype "passive"))
      (node (ref "S1") (pin "1") (pinfunction "S_1") (pintype "passive"))
      (node (ref "S1") (pin "2") (pinfunction "S1_2") (pintype "passive"))
    )
    (net (code "80") (name "VREG") (class "Default")
      (node (ref "C2") (pin "+") (pinfunction "+_+") (pintype "passive"))
      (node (ref "IC1") (pin "3") (pinfunction "VO_3") (pintype "passive"))
      (node (ref "S5") (pin "1") (pinfunction "O_1") (pintype "passive"))
    )
    (net (code "81") (name "unconnected-(JP5-Pad5)") (class "Default")
      (node (ref "JP5") (pin "5") (pinfunction "5_5") (pintype "passive"))
    )
    (net (code "82") (name "unconnected-(PICKIT-Pad6)") (class "Default")
      (node (ref "PICKIT") (pin "6") (pinfunction "6_6") (pintype "passive"))
    )
    (net (code "83") (name "unconnected-(X1-Pad2)") (class "Default")
      (node (ref "X1") (pin "2") (pinfunction "2_2") (pintype "passive"))
    )
    (net (code "84") (name "unconnected-(X1-Pad3)") (class "Default")
      (node (ref "X1") (pin "3") (pinfunction "3_3") (pintype "passive"))
    )
  )
)
